# soldeer.net
KiCad netlist of a schematic drawn in Altium Designer
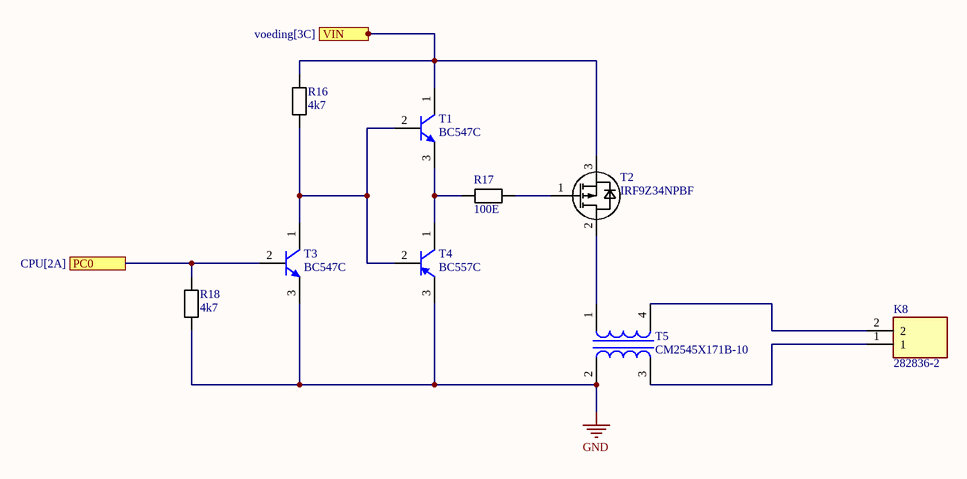
[diagram p0: soldeer.SchDoc]

(export (version "E")
  (design (tool "Eeschema 10.0.6"))
  (components
    (comp (ref "K8")
      (value "282836-2")
      (footprint "Schroefconnector 2 Pin")
      (description "Connector")
      (libsource (lib "soldeerstation") (part "Schroefconnector 2 Pin L"))
    )
    (comp (ref "R16")
      (value "4k7")
      (footprint "registor")
      (fields (field (name "MANUFACTURER") "Vishay Dale") (field (name "PART NUMBER") "CRCW08050000Z0EA"))
      (libsource (lib "Schlib1") (part "resistor"))
    )
    (comp (ref "R17")
      (value "100E")
      (footprint "registor")
      (fields (field (name "MANUFACTURER") "Vishay Dale") (field (name "PART NUMBER") "CRCW08050000Z0EA"))
      (libsource (lib "Schlib1") (part "resistor"))
    )
    (comp (ref "R18")
      (value "4k7")
      (footprint "registor")
      (fields (field (name "MANUFACTURER") "Vishay Dale") (field (name "PART NUMBER") "CRCW08050000Z0EA"))
      (libsource (lib "Schlib1") (part "resistor"))
    )
    (comp (ref "T1")
      (value "BC547C")
      (footprint "BC547C")
      (description "Amplifier Transistor, NPN Silicon, 3-Pin TO-92, Pb-Free, Bulk Box")
      (fields (field (name "MANUFACTURER") "On Semiconductor") (field (name "PARTNUMBER") "BC547CG"))
      (libsource (lib "soldeerstation") (part "BC547C"))
    )
    (comp (ref "T2")
      (value "IRF9Z34NPBF")
      (footprint "IRF9Z34NPBF")
      (description "OptiMOS - P2 Power-Transistor, P-channel-Enhancement mode, VDS -30V")
      (fields (field (name "MANUFACTURER") "Infineon Technologies"))
      (libsource (lib "soldeerstation") (part "IRF9Z34NPBF"))
    )
    (comp (ref "T3")
      (value "BC547C")
      (footprint "BC547C")
      (description "Amplifier Transistor, NPN Silicon, 3-Pin TO-92, Pb-Free, Bulk Box")
      (fields (field (name "MANUFACTURER") "On Semiconductor") (field (name "PARTNUMBER") "BC547CG"))
      (libsource (lib "soldeerstation") (part "BC547C"))
    )
    (comp (ref "T4")
      (value "BC557C")
      (footprint "BC557C")
      (description "Amplifier Transistor, PNP Silicon, 3-Pin TO-92, Bulk Box")
      (fields (field (name "MANUFACTURER") "On Semiconductor"))
      (libsource (lib "soldeerstation") (part "BC557C"))
    )
    (comp (ref "T5")
      (value "CM2545X171B-10")
      (footprint "CM2545X171B-10")
      (description "2 Line Common Mode Choke Through Hole 170 Ohms @ 100 MHz 10A DCR 10mOhm")
      (fields (field (name "MF") "Laird"))
      (libsource (lib "Schlib1") (part "CM2545X171B-10"))
    )
  )
  (nets
    (net (code "1") (name "/PC0") (class "Default")
      (node (ref "R18") (pin "2") (pinfunction "2_2") (pintype "passive"))
      (node (ref "T3") (pin "2") (pinfunction "B_2") (pintype "passive"))
    )
    (net (code "2") (name "/VIN") (class "Default")
      (node (ref "R16") (pin "2") (pinfunction "2_2") (pintype "passive"))
      (node (ref "T1") (pin "1") (pinfunction "C_1") (pintype "passive"))
      (node (ref "T2") (pin "3") (pinfunction "SOURCE_3") (pintype "passive"))
    )
    (net (code "3") (name "GND") (class "Default")
      (node (ref "R18") (pin "1") (pinfunction "1_1") (pintype "passive"))
      (node (ref "T3") (pin "3") (pinfunction "E_3") (pintype "passive"))
      (node (ref "T4") (pin "3") (pinfunction "E_3") (pintype "passive"))
      (node (ref "T5") (pin "2") (pinfunction "2_2") (pintype "passive"))
    )
    (net (code "4") (name "Net-(K8-Pad1)") (class "Default")
      (node (ref "K8") (pin "1") (pinfunction "1_1") (pintype "passive"))
      (node (ref "T5") (pin "3") (pinfunction "3_3") (pintype "passive"))
    )
    (net (code "5") (name "Net-(K8-Pad2)") (class "Default")
      (node (ref "K8") (pin "2") (pinfunction "2_2") (pintype "passive"))
      (node (ref "T5") (pin "4") (pinfunction "4_4") (pintype "passive"))
    )
    (net (code "6") (name "Net-(T1-B)") (class "Default")
      (node (ref "R16") (pin "1") (pinfunction "1_1") (pintype "passive"))
      (node (ref "T1") (pin "2") (pinfunction "B_2") (pintype "passive"))
      (node (ref "T3") (pin "1") (pinfunction "C_1") (pintype "passive"))
      (node (ref "T4") (pin "2") (pinfunction "B_2") (pintype "passive"))
    )
    (net (code "7") (name "Net-(T1-E)") (class "Default")
      (node (ref "R17") (pin "1") (pinfunction "1_1") (pintype "passive"))
      (node (ref "T1") (pin "3") (pinfunction "E_3") (pintype "passive"))
      (node (ref "T4") (pin "1") (pinfunction "C_1") (pintype "passive"))
    )
    (net (code "8") (name "Net-(T2-DRAIN)") (class "Default")
      (node (ref "T2") (pin "2") (pinfunction "DRAIN_2") (pintype "passive"))
      (node (ref "T5") (pin "1") (pinfunction "1_1") (pintype "passive"))
    )
    (net (code "9") (name "Net-(T2-GATE)") (class "Default")
      (node (ref "R17") (pin "2") (pinfunction "2_2") (pintype "passive"))
      (node (ref "T2") (pin "1") (pinfunction "GATE_1") (pintype "passive"))
    )
  )
)
